# Bluetooth_interface_-_RN42.net
KiCad netlist of a schematic drawn in Altium Designer
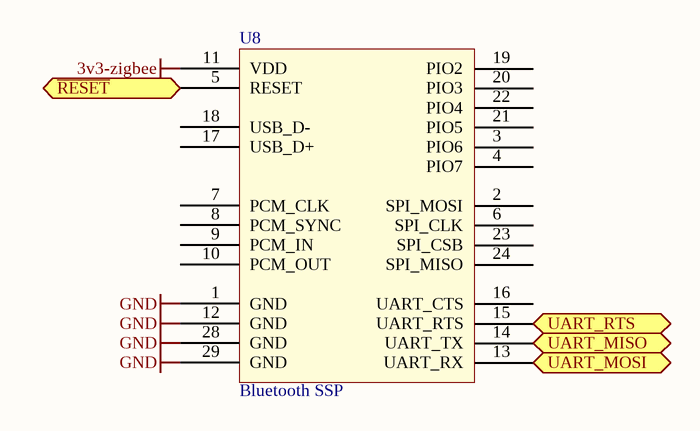
[diagram p0: Bluetooth interface - RN42.SchDoc]

(export (version "E")
  (design (tool "Eeschema 10.0.6"))
  (components
    (comp (ref "U8")
      (value "Bluetooth SSP")
      (footprint "BlueTooth_RN4x")
      (description "Wireless, Bluetooth")
      (fields (field (name "PART NUMBER") "BlueTooth-RN42"))
      (libsource (lib "OurDb") (part "Bluetooth-RN42SMD"))
    )
  )
  (nets
    (net (code "1") (name "/UART_MISO") (class "Default")
      (node (ref "U8") (pin "14") (pinfunction "UART_TX_14") (pintype "passive"))
    )
    (net (code "2") (name "/UART_MOSI") (class "Default")
      (node (ref "U8") (pin "13") (pinfunction "UART_RX_13") (pintype "passive"))
    )
    (net (code "3") (name "/UART_RTS") (class "Default")
      (node (ref "U8") (pin "15") (pinfunction "UART_RTS_15") (pintype "passive"))
    )
    (net (code "4") (name "/~{RESET}") (class "Default")
      (node (ref "U8") (pin "5") (pinfunction "RESET_5") (pintype "passive"))
    )
    (net (code "5") (name "3v3-zigbee") (class "Default")
      (node (ref "U8") (pin "11") (pinfunction "VDD_11") (pintype "passive"))
    )
    (net (code "6") (name "GND") (class "Default")
      (node (ref "U8") (pin "1") (pinfunction "GND_1") (pintype "passive"))
      (node (ref "U8") (pin "12") (pinfunction "GND_12") (pintype "passive"))
      (node (ref "U8") (pin "28") (pinfunction "GND_28") (pintype "passive"))
      (node (ref "U8") (pin "29") (pinfunction "GND_29") (pintype "passive"))
    )
    (net (code "7") (name "unconnected-(U8-PCM_CLK-Pad7)") (class "Default")
      (node (ref "U8") (pin "7") (pinfunction "PCM_CLK_7") (pintype "passive"))
    )
    (net (code "8") (name "unconnected-(U8-PCM_IN-Pad9)") (class "Default")
      (node (ref "U8") (pin "9") (pinfunction "PCM_IN_9") (pintype "passive"))
    )
    (net (code "9") (name "unconnected-(U8-PCM_OUT-Pad10)") (class "Default")
      (node (ref "U8") (pin "10") (pinfunction "PCM_OUT_10") (pintype "passive"))
    )
    (net (code "10") (name "unconnected-(U8-PCM_SYNC-Pad8)") (class "Default")
      (node (ref "U8") (pin "8") (pinfunction "PCM_SYNC_8") (pintype "passive"))
    )
    (net (code "11") (name "unconnected-(U8-PIO2-Pad19)") (class "Default")
      (node (ref "U8") (pin "19") (pinfunction "PIO2_19") (pintype "passive"))
    )
    (net (code "12") (name "unconnected-(U8-PIO3-Pad20)") (class "Default")
      (node (ref "U8") (pin "20") (pinfunction "PIO3_20") (pintype "passive"))
    )
    (net (code "13") (name "unconnected-(U8-PIO4-Pad22)") (class "Default")
      (node (ref "U8") (pin "22") (pinfunction "PIO4_22") (pintype "passive"))
    )
    (net (code "14") (name "unconnected-(U8-PIO5-Pad21)") (class "Default")
      (node (ref "U8") (pin "21") (pinfunction "PIO5_21") (pintype "passive"))
    )
    (net (code "15") (name "unconnected-(U8-PIO6-Pad3)") (class "Default")
      (node (ref "U8") (pin "3") (pinfunction "PIO6_3") (pintype "passive"))
    )
    (net (code "16") (name "unconnected-(U8-PIO7-Pad4)") (class "Default")
      (node (ref "U8") (pin "4") (pinfunction "PIO7_4") (pintype "passive"))
    )
    (net (code "17") (name "unconnected-(U8-SPI_CLK-Pad6)") (class "Default")
      (node (ref "U8") (pin "6") (pinfunction "SPI_CLK_6") (pintype "passive"))
    )
    (net (code "18") (name "unconnected-(U8-SPI_CSB-Pad23)") (class "Default")
      (node (ref "U8") (pin "23") (pinfunction "SPI_CSB_23") (pintype "passive"))
    )
    (net (code "19") (name "unconnected-(U8-SPI_MISO-Pad24)") (class "Default")
      (node (ref "U8") (pin "24") (pinfunction "SPI_MISO_24") (pintype "passive"))
    )
    (net (code "20") (name "unconnected-(U8-SPI_MOSI-Pad2)") (class "Default")
      (node (ref "U8") (pin "2") (pinfunction "SPI_MOSI_2") (pintype "passive"))
    )
    (net (code "21") (name "unconnected-(U8-UART_CTS-Pad16)") (class "Default")
      (node (ref "U8") (pin "16") (pinfunction "UART_CTS_16") (pintype "passive"))
    )
    (net (code "22") (name "unconnected-(U8-USB_D+-Pad17)") (class "Default")
      (node (ref "U8") (pin "17") (pinfunction "USB_D+_17") (pintype "passive"))
    )
    (net (code "23") (name "unconnected-(U8-USB_D--Pad18)") (class "Default")
      (node (ref "U8") (pin "18") (pinfunction "USB_D-_18") (pintype "passive"))
    )
  )
)
